# SST.net
KiCad netlist of a schematic drawn in Altium Designer
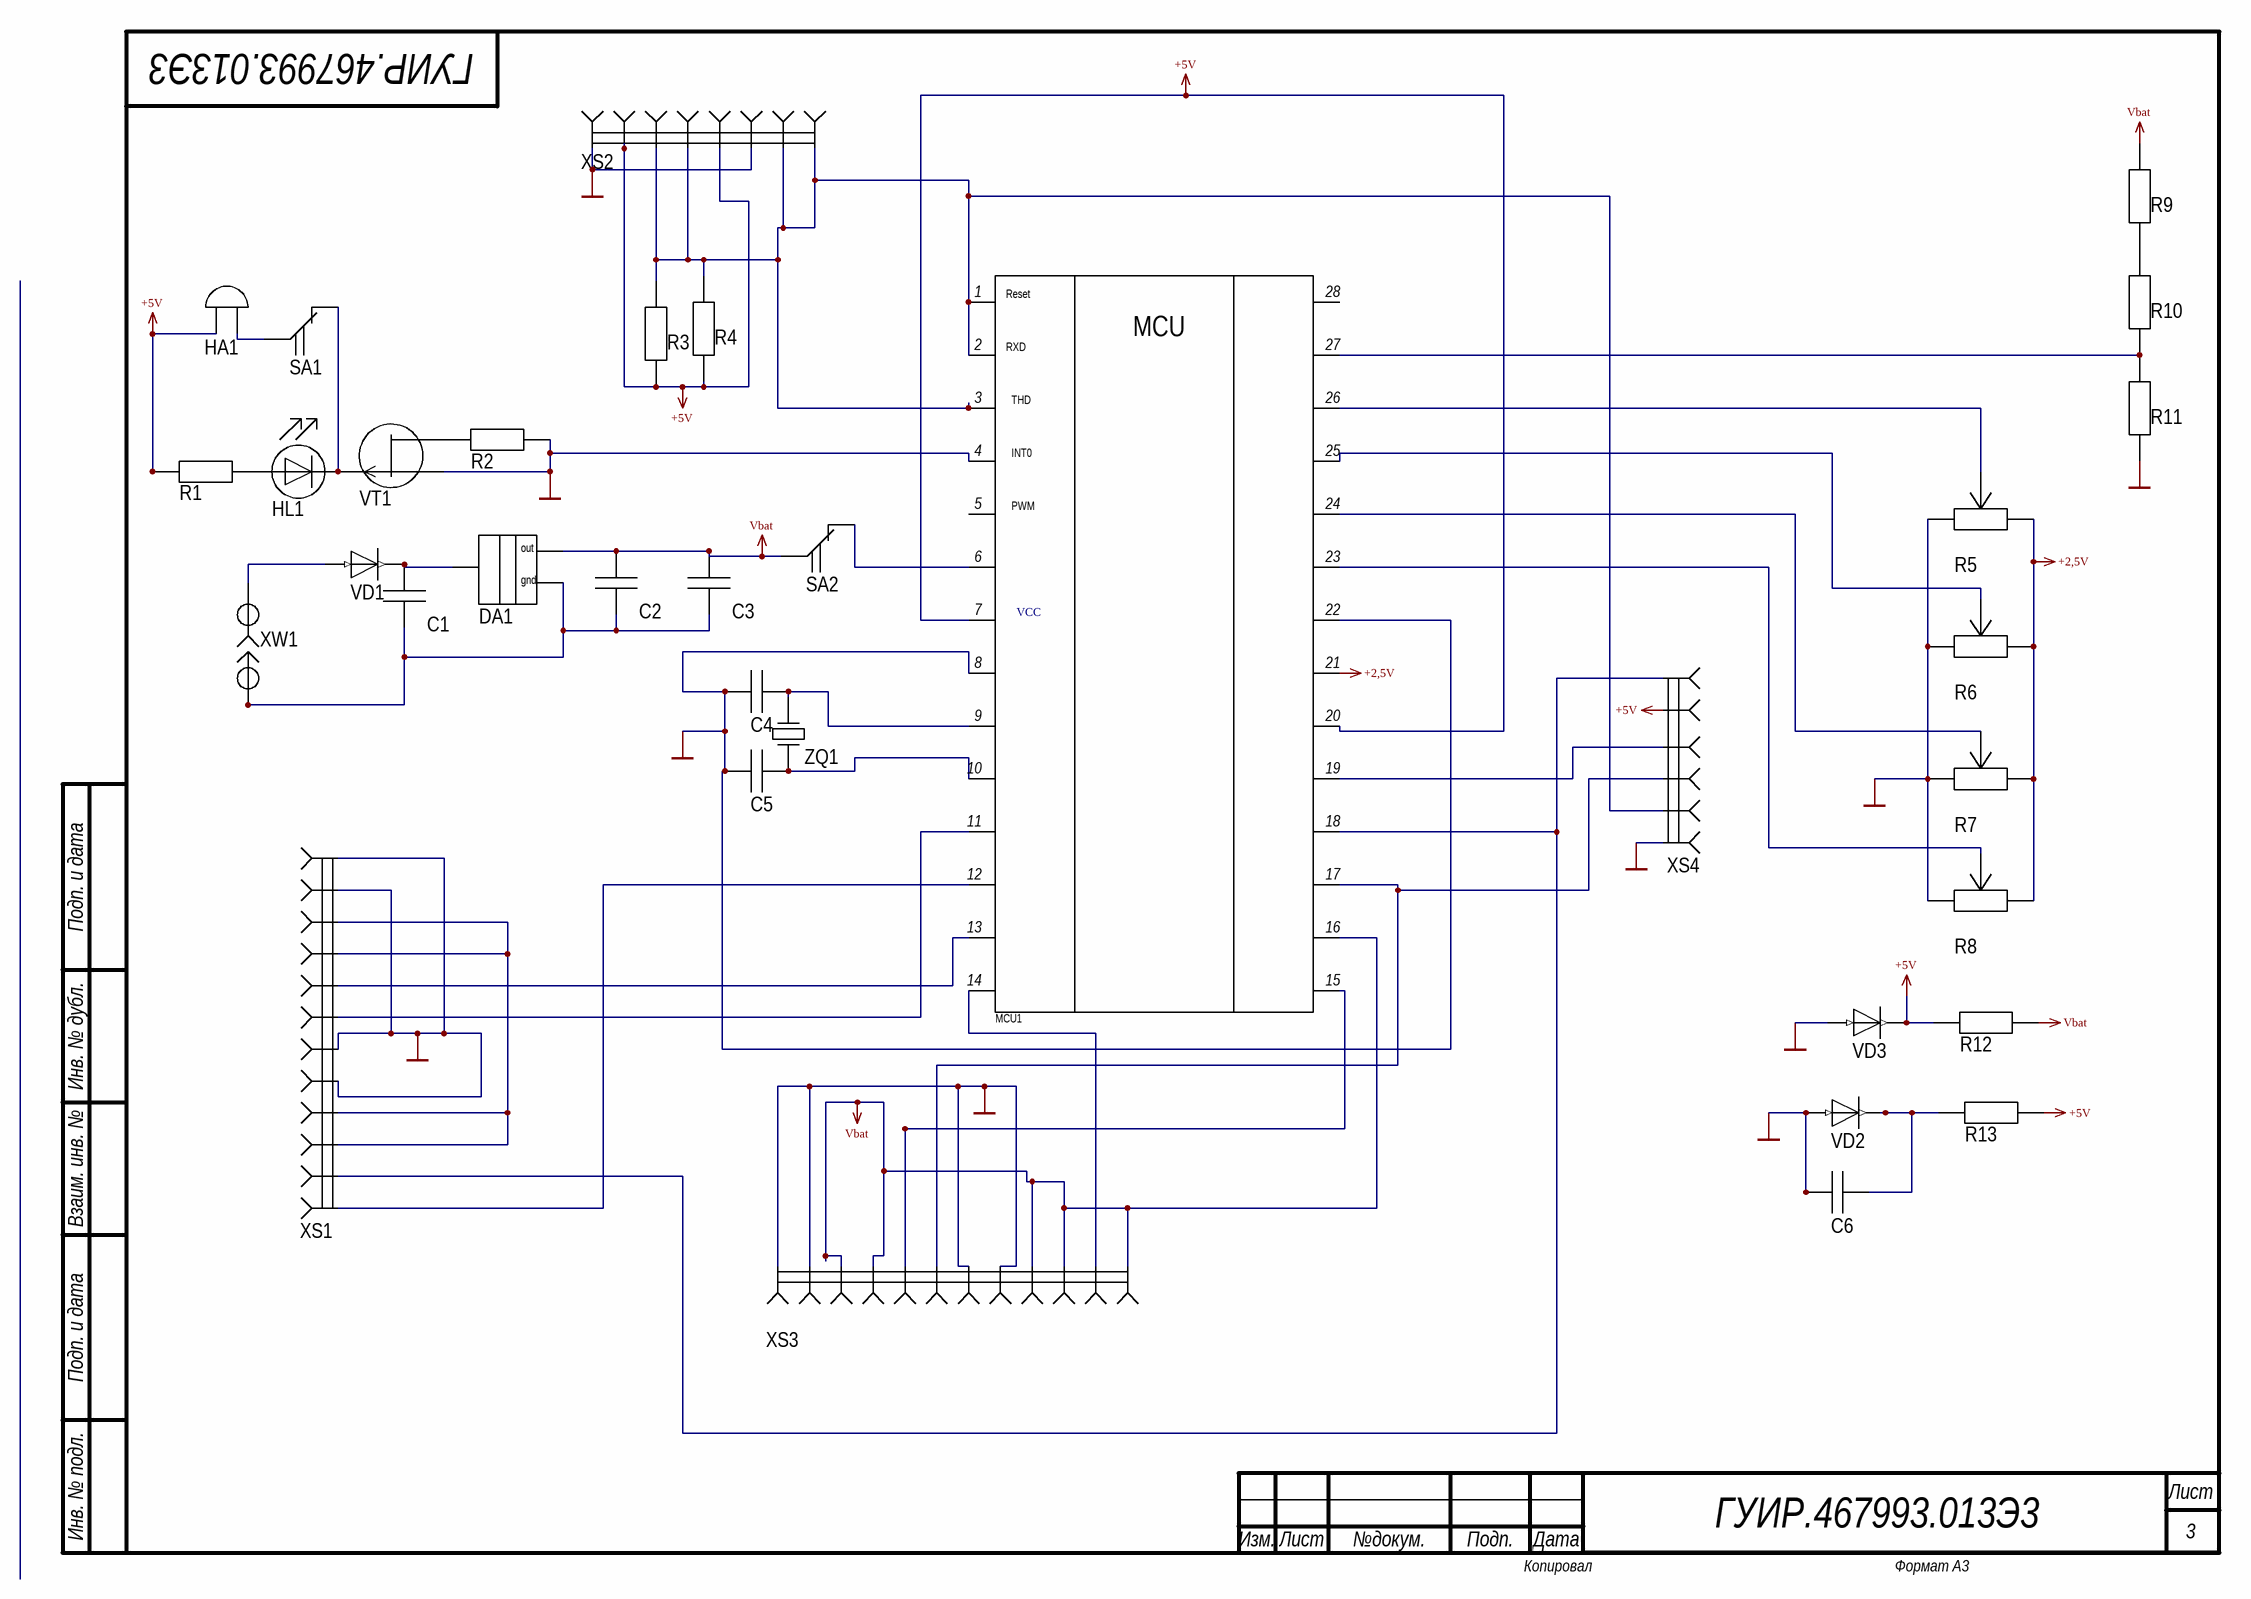
[diagram p0: SST.SchDoc]

(export (version "E")
  (design (tool "Eeschema 10.0.6"))
  (components
    (comp (ref "C1") (value "Capacitor") (libsource (lib "SST_Schlib") (part "Capacitor")))
    (comp (ref "C2") (value "Capacitor") (libsource (lib "SST_Schlib") (part "Capacitor")))
    (comp (ref "C3") (value "Capacitor") (libsource (lib "SST_Schlib") (part "Capacitor")))
    (comp (ref "C4") (value "Capacitor") (libsource (lib "SST_Schlib") (part "Capacitor")))
    (comp (ref "C5") (value "Capacitor") (libsource (lib "SST_Schlib") (part "Capacitor")))
    (comp (ref "C6") (value "Capacitor") (libsource (lib "SST_Schlib") (part "Capacitor")))
    (comp (ref "DA1") (value "voltage-regulator") (libsource (lib "SST_Schlib") (part "voltage-regulator")))
    (comp (ref "HA1") (value "Zummer") (libsource (lib "SST_Schlib") (part "Zummer")))
    (comp (ref "HL1") (value "LED") (libsource (lib "SST_Schlib") (part "LED")))
    (comp (ref "MCU1") (value "~") (libsource (lib "SST_Schlib") (part "Microcontroller")))
    (comp (ref "R1") (value "Resistor") (libsource (lib "") (part "Resistor_1")))
    (comp (ref "R2") (value "Resistor") (libsource (lib "") (part "Resistor_1")))
    (comp (ref "R3") (value "Resistor") (libsource (lib "") (part "Resistor_2")))
    (comp (ref "R4") (value "Resistor") (libsource (lib "SST_Schlib") (part "Resistor")))
    (comp (ref "R5") (value "potentiometer") (libsource (lib "SST_Schlib") (part "potentiometer")))
    (comp (ref "R6") (value "potentiometer") (libsource (lib "SST_Schlib") (part "potentiometer")))
    (comp (ref "R7") (value "potentiometer") (libsource (lib "SST_Schlib") (part "potentiometer")))
    (comp (ref "R8") (value "potentiometer") (libsource (lib "SST_Schlib") (part "potentiometer")))
    (comp (ref "R9") (value "Resistor") (libsource (lib "SST_Schlib") (part "Resistor")))
    (comp (ref "R10") (value "Resistor") (libsource (lib "SST_Schlib") (part "Resistor")))
    (comp (ref "R11") (value "Resistor") (libsource (lib "") (part "Resistor_2")))
    (comp (ref "R12") (value "Resistor") (libsource (lib "") (part "Resistor_1")))
    (comp (ref "R13") (value "Resistor") (libsource (lib "") (part "Resistor_1")))
    (comp (ref "SA1")
      (value "Switch")
      (description "Переключатели ползунковые 2П1Н")
      (libsource (lib "SST_Schlib") (part "Switch"))
    )
    (comp (ref "SA2")
      (value "Switch")
      (description "Переключатели ползунковые 2П1Н")
      (libsource (lib "SST_Schlib") (part "Switch"))
    )
    (comp (ref "VD1") (value "Diode") (libsource (lib "SST_Schlib") (part "Diode")))
    (comp (ref "VD2") (value "Diode") (libsource (lib "SST_Schlib") (part "Diode")))
    (comp (ref "VD3") (value "Diode") (libsource (lib "SST_Schlib") (part "Diode")))
    (comp (ref "VT1")
      (value "MOSFET")
      (description "Полевой с пэ каналом")
      (libsource (lib "SST_Schlib") (part "MOSFET"))
    )
    (comp (ref "XS1") (value "Сonnector12") (libsource (lib "SST_Schlib") (part "Сonnector12")))
    (comp (ref "XS2") (value "Сonnector8") (libsource (lib "SST_Schlib") (part "Сonnector8")))
    (comp (ref "XS3") (value "Сonnector12") (libsource (lib "SST_Schlib") (part "Сonnector12")))
    (comp (ref "XS4") (value "Сonnector6") (libsource (lib "SST_Schlib") (part "Сonnector6")))
    (comp (ref "XW1") (value "Сonnector_coaxial") (libsource (lib "SST_Schlib") (part "Сonnector_coaxial")))
    (comp (ref "ZQ1")
      (value "Xtal")
      (description "Резонатор кварцевый")
      (libsource (lib "SST_Schlib") (part "Xtal"))
    )
  )
  (nets
    (net (code "1") (name "+2,5V") (class "Default")
      (node (ref "MCU1") (pin "21") (pinfunction "21_21") (pintype "passive"))
      (node (ref "R5") (pin "2") (pinfunction "2_2") (pintype "passive"))
      (node (ref "R6") (pin "2") (pinfunction "2_2") (pintype "passive"))
      (node (ref "R7") (pin "2") (pinfunction "2_2") (pintype "passive"))
      (node (ref "R8") (pin "2") (pinfunction "2_2") (pintype "passive"))
    )
    (net (code "2") (name "+5V") (class "Default")
      (node (ref "HA1") (pin "1") (pinfunction "1_1") (pintype "passive"))
      (node (ref "MCU1") (pin "20") (pinfunction "20_20") (pintype "passive"))
      (node (ref "MCU1") (pin "7") (pinfunction "7_7") (pintype "passive"))
      (node (ref "R1") (pin "1") (pinfunction "*_1") (pintype "passive"))
      (node (ref "R12") (pin "1") (pinfunction "*_1") (pintype "passive"))
      (node (ref "R13") (pin "2") (pinfunction "2_2") (pintype "passive"))
      (node (ref "R3") (pin "2") (pinfunction "2_2") (pintype "passive"))
      (node (ref "R4") (pin "1") (pinfunction "*_1") (pintype "passive"))
      (node (ref "VD3") (pin "2") (pinfunction "2_2") (pintype "output"))
      (node (ref "XS2") (pin "4") (pinfunction "4_4") (pintype "passive"))
      (node (ref "XS2") (pin "8") (pinfunction "8_8") (pintype "passive"))
      (node (ref "XS4") (pin "5") (pinfunction "5_5") (pintype "passive"))
    )
    (net (code "3") (name "GND") (class "Default")
      (node (ref "C4") (pin "1") (pinfunction "1_1") (pintype "passive"))
      (node (ref "C4") (pin "17") (pinfunction "17_17") (pintype "passive"))
      (node (ref "C5") (pin "1") (pinfunction "1_1") (pintype "passive"))
      (node (ref "C5") (pin "17") (pinfunction "17_17") (pintype "passive"))
      (node (ref "C6") (pin "1") (pinfunction "1_1") (pintype "passive"))
      (node (ref "C6") (pin "17") (pinfunction "17_17") (pintype "passive"))
      (node (ref "MCU1") (pin "22") (pinfunction "22_22") (pintype "passive"))
      (node (ref "MCU1") (pin "4") (pinfunction "4_4") (pintype "passive"))
      (node (ref "MCU1") (pin "8") (pinfunction "8_8") (pintype "passive"))
      (node (ref "R11") (pin "2") (pinfunction "2_2") (pintype "passive"))
      (node (ref "R2") (pin "2") (pinfunction "2_2") (pintype "passive"))
      (node (ref "R5") (pin "1") (pinfunction "*_1") (pintype "passive"))
      (node (ref "R6") (pin "1") (pinfunction "*_1") (pintype "passive"))
      (node (ref "R7") (pin "1") (pinfunction "*_1") (pintype "passive"))
      (node (ref "R8") (pin "1") (pinfunction "*_1") (pintype "passive"))
      (node (ref "VD2") (pin "1") (pinfunction "1_1") (pintype "input"))
      (node (ref "VD3") (pin "1") (pinfunction "1_1") (pintype "input"))
      (node (ref "VT1") (pin "3") (pinfunction "3_3") (pintype "open_emitter"))
      (node (ref "XS1") (pin "1") (pinfunction "1_1") (pintype "passive"))
      (node (ref "XS1") (pin "2") (pinfunction "2_2") (pintype "passive"))
      (node (ref "XS2") (pin "3") (pinfunction "3_3") (pintype "passive"))
      (node (ref "XS2") (pin "7") (pinfunction "7_7") (pintype "passive"))
      (node (ref "XS3") (pin "1") (pinfunction "1_1") (pintype "passive"))
      (node (ref "XS3") (pin "2") (pinfunction "2_2") (pintype "passive"))
      (node (ref "XS4") (pin "1") (pinfunction "1_1") (pintype "passive"))
    )
    (net (code "4") (name "Net-(C1-Pad1)") (class "Default")
      (node (ref "C1") (pin "1") (pinfunction "1_1") (pintype "passive"))
      (node (ref "C1") (pin "17") (pinfunction "17_17") (pintype "passive"))
      (node (ref "DA1") (pin "1") (pinfunction "1_1") (pintype "passive"))
      (node (ref "VD1") (pin "2") (pinfunction "2_2") (pintype "output"))
    )
    (net (code "5") (name "Net-(C1-Pad2)") (class "Default")
      (node (ref "C1") (pin "2") (pinfunction "2_2") (pintype "passive"))
      (node (ref "C2") (pin "2") (pinfunction "2_2") (pintype "passive"))
      (node (ref "C3") (pin "2") (pinfunction "2_2") (pintype "passive"))
      (node (ref "DA1") (pin "3") (pinfunction "3_3") (pintype "passive"))
      (node (ref "XW1") (pin "2") (pinfunction "2_2") (pintype "passive"))
    )
    (net (code "6") (name "Net-(C4-Pad2)") (class "Default")
      (node (ref "C4") (pin "2") (pinfunction "2_2") (pintype "passive"))
      (node (ref "MCU1") (pin "9") (pinfunction "9_9") (pintype "passive"))
      (node (ref "ZQ1") (pin "2") (pinfunction "2_2") (pintype "passive"))
    )
    (net (code "7") (name "Net-(C5-Pad2)") (class "Default")
      (node (ref "C5") (pin "2") (pinfunction "2_2") (pintype "passive"))
      (node (ref "MCU1") (pin "10") (pinfunction "10_10") (pintype "passive"))
      (node (ref "ZQ1") (pin "1") (pinfunction "1_1") (pintype "passive"))
    )
    (net (code "8") (name "Net-(HA1-Pad2)") (class "Default")
      (node (ref "HA1") (pin "2") (pinfunction "2_2") (pintype "passive"))
      (node (ref "SA1") (pin "1") (pinfunction "1_1") (pintype "passive"))
    )
    (net (code "9") (name "Net-(HL1-Pad1)") (class "Default")
      (node (ref "HL1") (pin "1") (pinfunction "1_1") (pintype "passive"))
      (node (ref "R1") (pin "2") (pinfunction "2_2") (pintype "passive"))
    )
    (net (code "10") (name "Net-(HL1-Pad2)") (class "Default")
      (node (ref "HL1") (pin "2") (pinfunction "2_2") (pintype "passive"))
      (node (ref "SA1") (pin "2") (pinfunction "2_2") (pintype "passive"))
      (node (ref "VT1") (pin "1") (pinfunction "1_1") (pintype "passive"))
    )
    (net (code "11") (name "Net-(MCU1-Pad6)") (class "Default")
      (node (ref "MCU1") (pin "6") (pinfunction "6_6") (pintype "passive"))
      (node (ref "SA2") (pin "2") (pinfunction "2_2") (pintype "passive"))
    )
    (net (code "12") (name "Net-(MCU1-Pad11)") (class "Default")
      (node (ref "MCU1") (pin "11") (pinfunction "11_11") (pintype "passive"))
      (node (ref "XS1") (pin "6") (pinfunction "6_6") (pintype "passive"))
    )
    (net (code "13") (name "Net-(MCU1-Pad12)") (class "Default")
      (node (ref "MCU1") (pin "12") (pinfunction "12_12") (pintype "passive"))
      (node (ref "XS1") (pin "6") (pinfunction "6_6") (pintype "passive"))
    )
    (net (code "14") (name "Net-(MCU1-Pad13)") (class "Default")
      (node (ref "MCU1") (pin "13") (pinfunction "13_13") (pintype "passive"))
      (node (ref "XS1") (pin "5") (pinfunction "5_5") (pintype "passive"))
    )
    (net (code "15") (name "Net-(MCU1-Pad14)") (class "Default")
      (node (ref "MCU1") (pin "14") (pinfunction "14_14") (pintype "passive"))
      (node (ref "XS3") (pin "5") (pinfunction "5_5") (pintype "passive"))
    )
    (net (code "16") (name "Net-(MCU1-Pad15)") (class "Default")
      (node (ref "MCU1") (pin "15") (pinfunction "15_15") (pintype "passive"))
      (node (ref "XS3") (pin "5") (pinfunction "5_5") (pintype "passive"))
    )
    (net (code "17") (name "Net-(MCU1-Pad17)") (class "Default")
      (node (ref "MCU1") (pin "17") (pinfunction "17_17") (pintype "passive"))
      (node (ref "XS3") (pin "6") (pinfunction "6_6") (pintype "passive"))
      (node (ref "XS4") (pin "3") (pinfunction "3_3") (pintype "passive"))
    )
    (net (code "18") (name "Net-(MCU1-Pad18)") (class "Default")
      (node (ref "MCU1") (pin "18") (pinfunction "18_18") (pintype "passive"))
      (node (ref "XS1") (pin "5") (pinfunction "5_5") (pintype "passive"))
      (node (ref "XS4") (pin "6") (pinfunction "6_6") (pintype "passive"))
    )
    (net (code "19") (name "Net-(MCU1-Pad19)") (class "Default")
      (node (ref "MCU1") (pin "19") (pinfunction "19_19") (pintype "passive"))
      (node (ref "XS4") (pin "4") (pinfunction "4_4") (pintype "passive"))
    )
    (net (code "20") (name "Net-(MCU1-Pad23)") (class "Default")
      (node (ref "MCU1") (pin "23") (pinfunction "23_23") (pintype "passive"))
      (node (ref "R8") (pin "3") (pinfunction "3_3") (pintype "passive"))
    )
    (net (code "21") (name "Net-(MCU1-Pad24)") (class "Default")
      (node (ref "MCU1") (pin "24") (pinfunction "24_24") (pintype "passive"))
      (node (ref "R7") (pin "3") (pinfunction "3_3") (pintype "passive"))
    )
    (net (code "22") (name "Net-(MCU1-Pad25)") (class "Default")
      (node (ref "MCU1") (pin "25") (pinfunction "25_25") (pintype "passive"))
      (node (ref "R6") (pin "3") (pinfunction "3_3") (pintype "passive"))
    )
    (net (code "23") (name "Net-(MCU1-Pad26)") (class "Default")
      (node (ref "MCU1") (pin "26") (pinfunction "26_26") (pintype "passive"))
      (node (ref "R5") (pin "3") (pinfunction "3_3") (pintype "passive"))
    )
    (net (code "24") (name "Net-(R2-*)") (class "Default")
      (node (ref "R2") (pin "1") (pinfunction "*_1") (pintype "passive"))
      (node (ref "VT1") (pin "2") (pinfunction "2_2") (pintype "open_collector"))
    )
    (net (code "25") (name "Net-(R3-*)") (class "Default")
      (node (ref "MCU1") (pin "1") (pinfunction "1_1") (pintype "passive"))
      (node (ref "MCU1") (pin "2") (pinfunction "2_2") (pintype "passive"))
      (node (ref "MCU1") (pin "3") (pinfunction "3_3") (pintype "passive"))
      (node (ref "R3") (pin "1") (pinfunction "*_1") (pintype "passive"))
      (node (ref "R4") (pin "2") (pinfunction "2_2") (pintype "passive"))
      (node (ref "XS2") (pin "1") (pinfunction "1_1") (pintype "passive"))
      (node (ref "XS2") (pin "2") (pinfunction "2_2") (pintype "passive"))
      (node (ref "XS2") (pin "5") (pinfunction "5_5") (pintype "passive"))
      (node (ref "XS2") (pin "6") (pinfunction "6_6") (pintype "passive"))
      (node (ref "XS4") (pin "2") (pinfunction "2_2") (pintype "passive"))
    )
    (net (code "26") (name "Net-(R9-*)") (class "Default")
      (node (ref "R10") (pin "2") (pinfunction "2_2") (pintype "passive"))
      (node (ref "R9") (pin "1") (pinfunction "*_1") (pintype "passive"))
    )
    (net (code "27") (name "Net-(R10-*)") (class "Default")
      (node (ref "MCU1") (pin "27") (pinfunction "27_27") (pintype "passive"))
      (node (ref "R10") (pin "1") (pinfunction "*_1") (pintype "passive"))
      (node (ref "R11") (pin "1") (pinfunction "*_1") (pintype "passive"))
    )
    (net (code "28") (name "Net-(R13-*)") (class "Default")
      (node (ref "C6") (pin "2") (pinfunction "2_2") (pintype "passive"))
      (node (ref "R13") (pin "1") (pinfunction "*_1") (pintype "passive"))
      (node (ref "VD2") (pin "2") (pinfunction "2_2") (pintype "output"))
    )
    (net (code "29") (name "Net-(VD1-Pad1)") (class "Default")
      (node (ref "VD1") (pin "1") (pinfunction "1_1") (pintype "input"))
      (node (ref "XW1") (pin "1") (pinfunction "1_1") (pintype "passive"))
    )
    (net (code "30") (name "Net-(XS1-Pad3)") (class "Default")
      (node (ref "XS1") (pin "3") (pinfunction "3_3") (pintype "passive"))
      (node (ref "XS1") (pin "4") (pinfunction "4_4") (pintype "passive"))
      (node (ref "XS1") (pin "7") (pinfunction "7_7") (pintype "passive"))
    )
    (net (code "31") (name "Vbat") (class "Default")
      (node (ref "C2") (pin "1") (pinfunction "1_1") (pintype "passive"))
      (node (ref "C2") (pin "17") (pinfunction "17_17") (pintype "passive"))
      (node (ref "C3") (pin "1") (pinfunction "1_1") (pintype "passive"))
      (node (ref "C3") (pin "17") (pinfunction "17_17") (pintype "passive"))
      (node (ref "DA1") (pin "2") (pinfunction "2_2") (pintype "passive"))
      (node (ref "MCU1") (pin "16") (pinfunction "16_16") (pintype "passive"))
      (node (ref "R12") (pin "2") (pinfunction "2_2") (pintype "passive"))
      (node (ref "R9") (pin "2") (pinfunction "2_2") (pintype "passive"))
      (node (ref "SA2") (pin "1") (pinfunction "1_1") (pintype "passive"))
      (node (ref "XS3") (pin "3") (pinfunction "3_3") (pintype "passive"))
      (node (ref "XS3") (pin "4") (pinfunction "4_4") (pintype "passive"))
      (node (ref "XS3") (pin "6") (pinfunction "6_6") (pintype "passive"))
      (node (ref "XS3") (pin "7") (pinfunction "7_7") (pintype "passive"))
    )
    (net (code "32") (name "unconnected-(MCU1-Pad5)") (class "Default")
      (node (ref "MCU1") (pin "5") (pinfunction "5_5") (pintype "passive"))
    )
    (net (code "33") (name "unconnected-(MCU1-Pad28)") (class "Default")
      (node (ref "MCU1") (pin "28") (pinfunction "28_28") (pintype "passive"))
    )
  )
)
